# switch.net
KiCad netlist of a schematic drawn in EAGLE
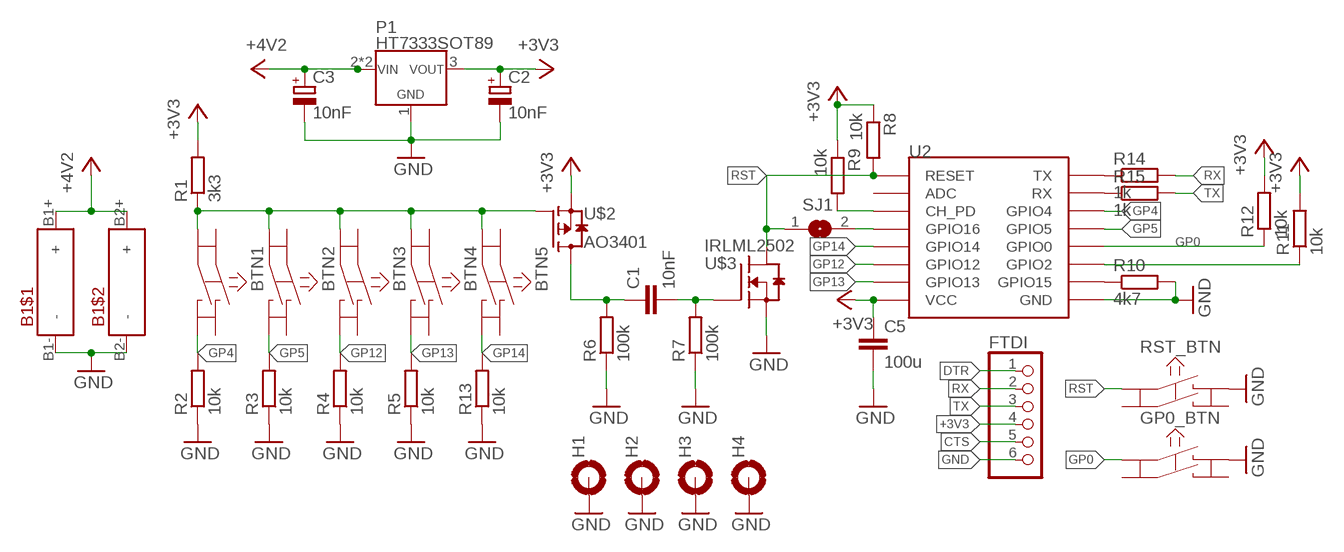
[diagram p0: schematic, sheet 1]

(export (version "E")
  (design (tool "Eeschema 10.0.6"))
  (components
    (comp (ref "B1")
      (value "18650_2X")
      (footprint "eagle-import:18650_HOLDER")
      (libsource (lib "eagle-import") (part "18650_2X"))
    )
    (comp (ref "BTN1")
      (value "KSM611A")
      (footprint "eagle-import:KSM611A")
      (libsource (lib "eagle-import") (part "KSM611A"))
    )
    (comp (ref "BTN2")
      (value "KSM611A")
      (footprint "eagle-import:KSM611A")
      (libsource (lib "eagle-import") (part "KSM611A"))
    )
    (comp (ref "BTN3")
      (value "KSM611A")
      (footprint "eagle-import:KSM611A")
      (libsource (lib "eagle-import") (part "KSM611A"))
    )
    (comp (ref "BTN4")
      (value "KSM611A")
      (footprint "eagle-import:KSM611A")
      (libsource (lib "eagle-import") (part "KSM611A"))
    )
    (comp (ref "BTN5")
      (value "KSM611A")
      (footprint "eagle-import:KSM611A")
      (libsource (lib "eagle-import") (part "KSM611A"))
    )
    (comp (ref "C1")
      (value "10nF")
      (footprint "eagle-import:C025-025X050")
      (libsource (lib "eagle-import") (part "C-EU025-025X050"))
    )
    (comp (ref "C2")
      (value "10nF")
      (footprint "eagle-import:E5-8,5")
      (libsource (lib "eagle-import") (part "CPOL-EUE5-8.5"))
    )
    (comp (ref "C3")
      (value "10nF")
      (footprint "eagle-import:E5-8,5")
      (libsource (lib "eagle-import") (part "CPOL-EUE5-8.5"))
    )
    (comp (ref "C5")
      (value "100u")
      (footprint "eagle-import:C1206")
      (libsource (lib "eagle-import") (part "C-EUC1206"))
    )
    (comp (ref "FTDI")
      (value "PINHD-1X06_2.54-S")
      (footprint "eagle-import:1X06-S")
      (libsource (lib "eagle-import") (part "PINHD-1X06_2.54-S"))
    )
    (comp (ref "GP0_BTN")
      (value "KSM611A")
      (footprint "eagle-import:KSM611A")
      (libsource (lib "eagle-import") (part "KSM611A"))
    )
    (comp (ref "H1")
      (value "MOUNT-PAD-ROUND3.2")
      (footprint "eagle-import:3,2-PAD")
      (libsource (lib "eagle-import") (part "MOUNT-PAD-ROUND3.2"))
    )
    (comp (ref "H2")
      (value "MOUNT-PAD-ROUND3.2")
      (footprint "eagle-import:3,2-PAD")
      (libsource (lib "eagle-import") (part "MOUNT-PAD-ROUND3.2"))
    )
    (comp (ref "H3")
      (value "MOUNT-PAD-ROUND3.2")
      (footprint "eagle-import:3,2-PAD")
      (libsource (lib "eagle-import") (part "MOUNT-PAD-ROUND3.2"))
    )
    (comp (ref "H4")
      (value "MOUNT-PAD-ROUND3.2")
      (footprint "eagle-import:3,2-PAD")
      (libsource (lib "eagle-import") (part "MOUNT-PAD-ROUND3.2"))
    )
    (comp (ref "P1")
      (value "HT7333SOT89")
      (footprint "eagle-import:SOT89")
      (libsource (lib "eagle-import") (part "HT7333SOT89"))
    )
    (comp (ref "R1")
      (value "3k3")
      (footprint "eagle-import:MULTI_RESISTOR")
      (libsource (lib "eagle-import") (part "R-EU_MULTI"))
    )
    (comp (ref "R2")
      (value "10k")
      (footprint "eagle-import:MULTI_RESISTOR")
      (libsource (lib "eagle-import") (part "R-EU_MULTI"))
    )
    (comp (ref "R3")
      (value "10k")
      (footprint "eagle-import:MULTI_RESISTOR")
      (libsource (lib "eagle-import") (part "R-EU_MULTI"))
    )
    (comp (ref "R4")
      (value "10k")
      (footprint "eagle-import:MULTI_RESISTOR")
      (libsource (lib "eagle-import") (part "R-EU_MULTI"))
    )
    (comp (ref "R5")
      (value "10k")
      (footprint "eagle-import:MULTI_RESISTOR")
      (libsource (lib "eagle-import") (part "R-EU_MULTI"))
    )
    (comp (ref "R6")
      (value "100k")
      (footprint "eagle-import:MULTI_RESISTOR")
      (libsource (lib "eagle-import") (part "R-EU_MULTI"))
    )
    (comp (ref "R7")
      (value "100k")
      (footprint "eagle-import:MULTI_RESISTOR")
      (libsource (lib "eagle-import") (part "R-EU_MULTI"))
    )
    (comp (ref "R8")
      (value "10k")
      (footprint "eagle-import:MULTI_RESISTOR")
      (libsource (lib "eagle-import") (part "R-EU_MULTI"))
    )
    (comp (ref "R9")
      (value "10k")
      (footprint "eagle-import:MULTI_RESISTOR")
      (libsource (lib "eagle-import") (part "R-EU_MULTI"))
    )
    (comp (ref "R10")
      (value "4k7")
      (footprint "eagle-import:MULTI_RESISTOR")
      (libsource (lib "eagle-import") (part "R-EU_MULTI"))
    )
    (comp (ref "R11")
      (value "10k")
      (footprint "eagle-import:MULTI_RESISTOR")
      (libsource (lib "eagle-import") (part "R-EU_MULTI"))
    )
    (comp (ref "R12")
      (value "10k")
      (footprint "eagle-import:MULTI_RESISTOR")
      (libsource (lib "eagle-import") (part "R-EU_MULTI"))
    )
    (comp (ref "R13")
      (value "10k")
      (footprint "eagle-import:MULTI_RESISTOR")
      (libsource (lib "eagle-import") (part "R-EU_MULTI"))
    )
    (comp (ref "R14")
      (value "1k")
      (footprint "eagle-import:MULTI_RESISTOR")
      (libsource (lib "eagle-import") (part "R-EU_MULTI"))
    )
    (comp (ref "R15")
      (value "1k")
      (footprint "eagle-import:MULTI_RESISTOR")
      (libsource (lib "eagle-import") (part "R-EU_MULTI"))
    )
    (comp (ref "RST_BTN")
      (value "KSM611A")
      (footprint "eagle-import:KSM611A")
      (libsource (lib "eagle-import") (part "KSM611A"))
    )
    (comp (ref "SJ1") (value "SJ") (footprint "eagle-import:SJ") (libsource (lib "eagle-import") (part "SJ")))
    (comp (ref "U$2")
      (value "AO3401")
      (footprint "eagle-import:SOT23")
      (libsource (lib "eagle-import") (part "P-CH_AO3401"))
    )
    (comp (ref "U$3")
      (value "IRLML2502")
      (footprint "eagle-import:SOT23")
      (libsource (lib "eagle-import") (part "N-CH_IRLML2502"))
    )
    (comp (ref "U2")
      (value "ESP12SMD")
      (footprint "eagle-import:ESP12-SMD")
      (libsource (lib "eagle-import") (part "ESP12SMD"))
    )
  )
  (nets
    (net (code "1") (name "+3V3") (class "Default")
      (node (ref "C2") (pin "+") (pinfunction "+_+") (pintype "passive"))
      (node (ref "C5") (pin "1") (pinfunction "1_1") (pintype "passive"))
      (node (ref "FTDI") (pin "4") (pinfunction "4_4") (pintype "passive"))
      (node (ref "P1") (pin "3") (pinfunction "VOUT_3") (pintype "power_in"))
      (node (ref "R1") (pin "2@1") (pinfunction "2_2@1") (pintype "passive"))
      (node (ref "R1") (pin "2@2") (pinfunction "2_2@2") (pintype "passive"))
      (node (ref "R11") (pin "2@1") (pinfunction "2_2@1") (pintype "passive"))
      (node (ref "R11") (pin "2@2") (pinfunction "2_2@2") (pintype "passive"))
      (node (ref "R12") (pin "2@1") (pinfunction "2_2@1") (pintype "passive"))
      (node (ref "R12") (pin "2@2") (pinfunction "2_2@2") (pintype "passive"))
      (node (ref "R8") (pin "1@1") (pinfunction "1_1@1") (pintype "passive"))
      (node (ref "R8") (pin "1@2") (pinfunction "1_1@2") (pintype "passive"))
      (node (ref "R9") (pin "1@1") (pinfunction "1_1@1") (pintype "passive"))
      (node (ref "R9") (pin "1@2") (pinfunction "1_1@2") (pintype "passive"))
      (node (ref "U$2") (pin "2") (pinfunction "S_2") (pintype "passive"))
      (node (ref "U2") (pin "VCC") (pinfunction "VCC_VCC") (pintype "bidirectional"))
    )
    (net (code "2") (name "+4V2") (class "Default")
      (node (ref "B1") (pin "B1+") (pinfunction "+_B1+") (pintype "power_in"))
      (node (ref "B1") (pin "B2+") (pinfunction "+_B2+") (pintype "power_in"))
      (node (ref "C3") (pin "+") (pinfunction "+_+") (pintype "passive"))
      (node (ref "P1") (pin "2") (pinfunction "VIN_2") (pintype "power_in"))
      (node (ref "P1") (pin "2@1") (pinfunction "VIN_2@1") (pintype "power_in"))
    )
    (net (code "3") (name "CTS") (class "Default")
      (node (ref "FTDI") (pin "5") (pinfunction "5_5") (pintype "passive"))
    )
    (net (code "4") (name "DTR") (class "Default")
      (node (ref "FTDI") (pin "1") (pinfunction "1_1") (pintype "passive"))
    )
    (net (code "5") (name "GND") (class "Default")
      (node (ref "B1") (pin "B1-") (pinfunction "-_B1-") (pintype "power_in"))
      (node (ref "B1") (pin "B2-") (pinfunction "-_B2-") (pintype "power_in"))
      (node (ref "C2") (pin "-") (pinfunction "-_-") (pintype "passive"))
      (node (ref "C3") (pin "-") (pinfunction "-_-") (pintype "passive"))
      (node (ref "C5") (pin "2") (pinfunction "2_2") (pintype "passive"))
      (node (ref "FTDI") (pin "6") (pinfunction "6_6") (pintype "passive"))
      (node (ref "GP0_BTN") (pin "B") (pinfunction "B_B") (pintype "passive"))
      (node (ref "H1") (pin "B3,2") (pinfunction "MOUNT_B3,2") (pintype "passive"))
      (node (ref "H2") (pin "B3,2") (pinfunction "MOUNT_B3,2") (pintype "passive"))
      (node (ref "H3") (pin "B3,2") (pinfunction "MOUNT_B3,2") (pintype "passive"))
      (node (ref "H4") (pin "B3,2") (pinfunction "MOUNT_B3,2") (pintype "passive"))
      (node (ref "P1") (pin "1") (pinfunction "GND_1") (pintype "power_in"))
      (node (ref "R10") (pin "2@1") (pinfunction "2_2@1") (pintype "passive"))
      (node (ref "R10") (pin "2@2") (pinfunction "2_2@2") (pintype "passive"))
      (node (ref "R13") (pin "1@1") (pinfunction "1_1@1") (pintype "passive"))
      (node (ref "R13") (pin "1@2") (pinfunction "1_1@2") (pintype "passive"))
      (node (ref "R2") (pin "1@1") (pinfunction "1_1@1") (pintype "passive"))
      (node (ref "R2") (pin "1@2") (pinfunction "1_1@2") (pintype "passive"))
      (node (ref "R3") (pin "1@1") (pinfunction "1_1@1") (pintype "passive"))
      (node (ref "R3") (pin "1@2") (pinfunction "1_1@2") (pintype "passive"))
      (node (ref "R4") (pin "1@1") (pinfunction "1_1@1") (pintype "passive"))
      (node (ref "R4") (pin "1@2") (pinfunction "1_1@2") (pintype "passive"))
      (node (ref "R5") (pin "1@1") (pinfunction "1_1@1") (pintype "passive"))
      (node (ref "R5") (pin "1@2") (pinfunction "1_1@2") (pintype "passive"))
      (node (ref "R6") (pin "1@1") (pinfunction "1_1@1") (pintype "passive"))
      (node (ref "R6") (pin "1@2") (pinfunction "1_1@2") (pintype "passive"))
      (node (ref "R7") (pin "1@1") (pinfunction "1_1@1") (pintype "passive"))
      (node (ref "R7") (pin "1@2") (pinfunction "1_1@2") (pintype "passive"))
      (node (ref "RST_BTN") (pin "B") (pinfunction "B_B") (pintype "passive"))
      (node (ref "U$3") (pin "2") (pinfunction "S_2") (pintype "passive"))
      (node (ref "U2") (pin "GND") (pinfunction "GND_GND") (pintype "bidirectional"))
    )
    (net (code "6") (name "GP0") (class "Default")
      (node (ref "GP0_BTN") (pin "A") (pinfunction "A_A") (pintype "passive"))
      (node (ref "R12") (pin "1@1") (pinfunction "1_1@1") (pintype "passive"))
      (node (ref "R12") (pin "1@2") (pinfunction "1_1@2") (pintype "passive"))
      (node (ref "U2") (pin "GPIO0") (pinfunction "GPIO0_GPIO0") (pintype "bidirectional"))
    )
    (net (code "7") (name "GP4") (class "Default")
      (node (ref "BTN1") (pin "D") (pinfunction "D_D") (pintype "passive"))
      (node (ref "R2") (pin "2@1") (pinfunction "2_2@1") (pintype "passive"))
      (node (ref "R2") (pin "2@2") (pinfunction "2_2@2") (pintype "passive"))
      (node (ref "U2") (pin "GPIO4") (pinfunction "GPIO4_GPIO4") (pintype "bidirectional"))
    )
    (net (code "8") (name "GP5") (class "Default")
      (node (ref "BTN2") (pin "D") (pinfunction "D_D") (pintype "passive"))
      (node (ref "R3") (pin "2@1") (pinfunction "2_2@1") (pintype "passive"))
      (node (ref "R3") (pin "2@2") (pinfunction "2_2@2") (pintype "passive"))
      (node (ref "U2") (pin "GPIO5") (pinfunction "GPIO5_GPIO5") (pintype "bidirectional"))
    )
    (net (code "9") (name "GP12") (class "Default")
      (node (ref "BTN3") (pin "D") (pinfunction "D_D") (pintype "passive"))
      (node (ref "R4") (pin "2@1") (pinfunction "2_2@1") (pintype "passive"))
      (node (ref "R4") (pin "2@2") (pinfunction "2_2@2") (pintype "passive"))
      (node (ref "U2") (pin "GPIO12") (pinfunction "GPIO12_GPIO12") (pintype "bidirectional"))
    )
    (net (code "10") (name "GP13") (class "Default")
      (node (ref "BTN4") (pin "D") (pinfunction "D_D") (pintype "passive"))
      (node (ref "R5") (pin "2@1") (pinfunction "2_2@1") (pintype "passive"))
      (node (ref "R5") (pin "2@2") (pinfunction "2_2@2") (pintype "passive"))
      (node (ref "U2") (pin "GPIO13") (pinfunction "GPIO13_GPIO13") (pintype "bidirectional"))
    )
    (net (code "11") (name "GP14") (class "Default")
      (node (ref "BTN5") (pin "D") (pinfunction "D_D") (pintype "passive"))
      (node (ref "R13") (pin "2@1") (pinfunction "2_2@1") (pintype "passive"))
      (node (ref "R13") (pin "2@2") (pinfunction "2_2@2") (pintype "passive"))
      (node (ref "U2") (pin "GPIO14") (pinfunction "GPIO14_GPIO14") (pintype "bidirectional"))
    )
    (net (code "12") (name "Net-(R9-2-Pad2@1)") (class "Default")
      (node (ref "R9") (pin "2@1") (pinfunction "2_2@1") (pintype "passive"))
      (node (ref "R9") (pin "2@2") (pinfunction "2_2@2") (pintype "passive"))
      (node (ref "U2") (pin "CH_PD") (pinfunction "CH_PD_CH_PD") (pintype "bidirectional"))
    )
    (net (code "13") (name "Net-(R10-1-Pad1@1)") (class "Default")
      (node (ref "R10") (pin "1@1") (pinfunction "1_1@1") (pintype "passive"))
      (node (ref "R10") (pin "1@2") (pinfunction "1_1@2") (pintype "passive"))
      (node (ref "U2") (pin "GPIO15") (pinfunction "GPIO15_GPIO15") (pintype "bidirectional"))
    )
    (net (code "14") (name "Net-(R11-1-Pad1@1)") (class "Default")
      (node (ref "R11") (pin "1@1") (pinfunction "1_1@1") (pintype "passive"))
      (node (ref "R11") (pin "1@2") (pinfunction "1_1@2") (pintype "passive"))
      (node (ref "U2") (pin "GPIO2") (pinfunction "GPIO2_GPIO2") (pintype "bidirectional"))
    )
    (net (code "15") (name "Net-(SJ1-Pad2)") (class "Default")
      (node (ref "SJ1") (pin "2") (pinfunction "2_2") (pintype "passive"))
      (node (ref "U2") (pin "GPIO16") (pinfunction "GPIO16_GPIO16") (pintype "bidirectional"))
    )
    (net (code "16") (name "Net-(U$2-D)") (class "Default")
      (node (ref "C1") (pin "1") (pinfunction "1_1") (pintype "passive"))
      (node (ref "R6") (pin "2@1") (pinfunction "2_2@1") (pintype "passive"))
      (node (ref "R6") (pin "2@2") (pinfunction "2_2@2") (pintype "passive"))
      (node (ref "U$2") (pin "3") (pinfunction "D_3") (pintype "passive"))
    )
    (net (code "17") (name "Net-(U$2-G)") (class "Default")
      (node (ref "BTN1") (pin "C") (pinfunction "C_C") (pintype "passive"))
      (node (ref "BTN2") (pin "C") (pinfunction "C_C") (pintype "passive"))
      (node (ref "BTN3") (pin "C") (pinfunction "C_C") (pintype "passive"))
      (node (ref "BTN4") (pin "C") (pinfunction "C_C") (pintype "passive"))
      (node (ref "BTN5") (pin "C") (pinfunction "C_C") (pintype "passive"))
      (node (ref "R1") (pin "1@1") (pinfunction "1_1@1") (pintype "passive"))
      (node (ref "R1") (pin "1@2") (pinfunction "1_1@2") (pintype "passive"))
      (node (ref "U$2") (pin "1") (pinfunction "G_1") (pintype "passive"))
    )
    (net (code "18") (name "Net-(U$3-G)") (class "Default")
      (node (ref "C1") (pin "2") (pinfunction "2_2") (pintype "passive"))
      (node (ref "R7") (pin "2@1") (pinfunction "2_2@1") (pintype "passive"))
      (node (ref "R7") (pin "2@2") (pinfunction "2_2@2") (pintype "passive"))
      (node (ref "U$3") (pin "1") (pinfunction "G_1") (pintype "passive"))
    )
    (net (code "19") (name "Net-(U2-RX)") (class "Default")
      (node (ref "R15") (pin "1@1") (pinfunction "1_1@1") (pintype "passive"))
      (node (ref "R15") (pin "1@2") (pinfunction "1_1@2") (pintype "passive"))
      (node (ref "U2") (pin "RXD0") (pinfunction "RX_RXD0") (pintype "bidirectional"))
    )
    (net (code "20") (name "Net-(U2-TX)") (class "Default")
      (node (ref "R14") (pin "1@1") (pinfunction "1_1@1") (pintype "passive"))
      (node (ref "R14") (pin "1@2") (pinfunction "1_1@2") (pintype "passive"))
      (node (ref "U2") (pin "TXD0") (pinfunction "TX_TXD0") (pintype "bidirectional"))
    )
    (net (code "21") (name "RST") (class "Default")
      (node (ref "R8") (pin "2@1") (pinfunction "2_2@1") (pintype "passive"))
      (node (ref "R8") (pin "2@2") (pinfunction "2_2@2") (pintype "passive"))
      (node (ref "RST_BTN") (pin "A") (pinfunction "A_A") (pintype "passive"))
      (node (ref "SJ1") (pin "1") (pinfunction "1_1") (pintype "passive"))
      (node (ref "U$3") (pin "3") (pinfunction "D_3") (pintype "passive"))
      (node (ref "U2") (pin "RESET") (pinfunction "RESET_RESET") (pintype "bidirectional"))
    )
    (net (code "22") (name "RX") (class "Default")
      (node (ref "FTDI") (pin "2") (pinfunction "2_2") (pintype "passive"))
      (node (ref "R14") (pin "2@1") (pinfunction "2_2@1") (pintype "passive"))
      (node (ref "R14") (pin "2@2") (pinfunction "2_2@2") (pintype "passive"))
    )
    (net (code "23") (name "TX") (class "Default")
      (node (ref "FTDI") (pin "3") (pinfunction "3_3") (pintype "passive"))
      (node (ref "R15") (pin "2@1") (pinfunction "2_2@1") (pintype "passive"))
      (node (ref "R15") (pin "2@2") (pinfunction "2_2@2") (pintype "passive"))
    )
    (net (code "24") (name "unconnected-(BTN1-PadA)") (class "Default")
      (node (ref "BTN1") (pin "A") (pinfunction "A_A") (pintype "passive"))
    )
    (net (code "25") (name "unconnected-(BTN1-PadB)") (class "Default")
      (node (ref "BTN1") (pin "B") (pinfunction "B_B") (pintype "passive"))
    )
    (net (code "26") (name "unconnected-(BTN2-PadA)") (class "Default")
      (node (ref "BTN2") (pin "A") (pinfunction "A_A") (pintype "passive"))
    )
    (net (code "27") (name "unconnected-(BTN2-PadB)") (class "Default")
      (node (ref "BTN2") (pin "B") (pinfunction "B_B") (pintype "passive"))
    )
    (net (code "28") (name "unconnected-(BTN3-PadA)") (class "Default")
      (node (ref "BTN3") (pin "A") (pinfunction "A_A") (pintype "passive"))
    )
    (net (code "29") (name "unconnected-(BTN3-PadB)") (class "Default")
      (node (ref "BTN3") (pin "B") (pinfunction "B_B") (pintype "passive"))
    )
    (net (code "30") (name "unconnected-(BTN4-PadA)") (class "Default")
      (node (ref "BTN4") (pin "A") (pinfunction "A_A") (pintype "passive"))
    )
    (net (code "31") (name "unconnected-(BTN4-PadB)") (class "Default")
      (node (ref "BTN4") (pin "B") (pinfunction "B_B") (pintype "passive"))
    )
    (net (code "32") (name "unconnected-(BTN5-PadA)") (class "Default")
      (node (ref "BTN5") (pin "A") (pinfunction "A_A") (pintype "passive"))
    )
    (net (code "33") (name "unconnected-(BTN5-PadB)") (class "Default")
      (node (ref "BTN5") (pin "B") (pinfunction "B_B") (pintype "passive"))
    )
    (net (code "34") (name "unconnected-(GP0_BTN-PadC)") (class "Default")
      (node (ref "GP0_BTN") (pin "C") (pinfunction "C_C") (pintype "passive"))
    )
    (net (code "35") (name "unconnected-(GP0_BTN-PadD)") (class "Default")
      (node (ref "GP0_BTN") (pin "D") (pinfunction "D_D") (pintype "passive"))
    )
    (net (code "36") (name "unconnected-(RST_BTN-PadC)") (class "Default")
      (node (ref "RST_BTN") (pin "C") (pinfunction "C_C") (pintype "passive"))
    )
    (net (code "37") (name "unconnected-(RST_BTN-PadD)") (class "Default")
      (node (ref "RST_BTN") (pin "D") (pinfunction "D_D") (pintype "passive"))
    )
    (net (code "38") (name "unconnected-(U2-PadADC)") (class "Default")
      (node (ref "U2") (pin "ADC") (pinfunction "ADC_ADC") (pintype "bidirectional"))
    )
  )
)
